# SELE_async.net
KiCad netlist of a schematic drawn in EasyEDA
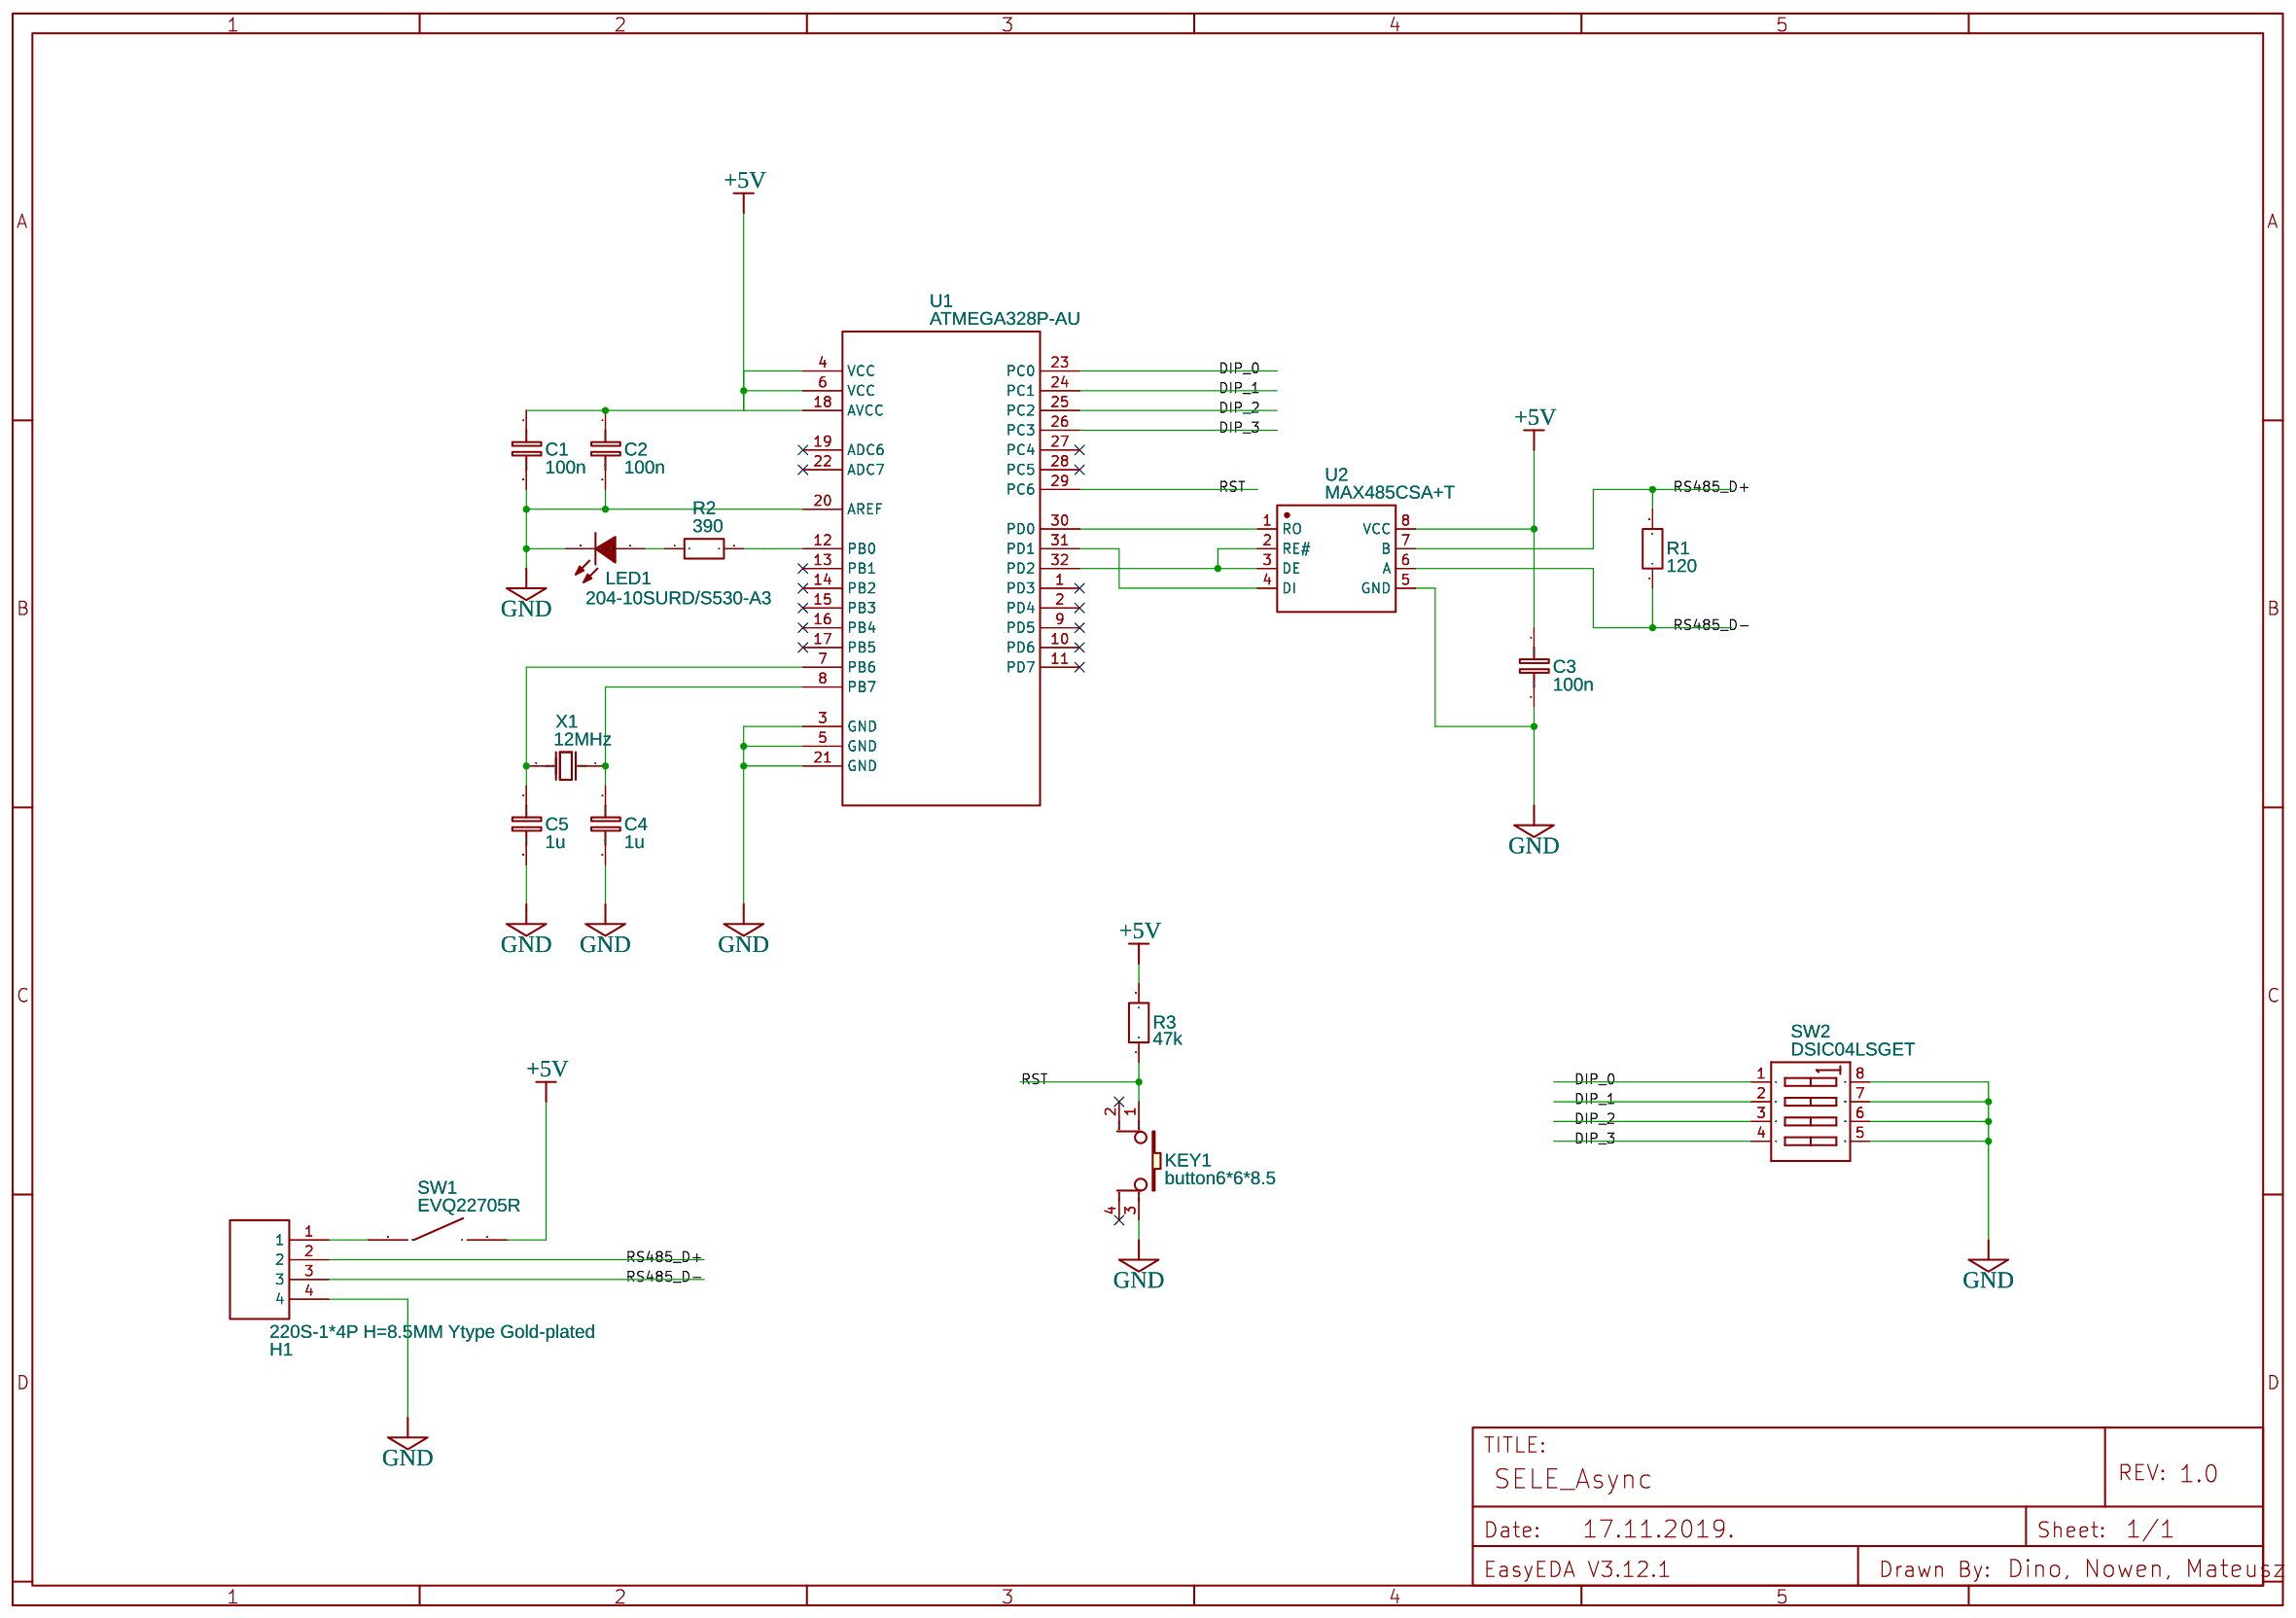
[diagram p0: schematic sheet]

(export (version "E")
  (design (tool "Eeschema 10.0.6"))
  (components
    (comp (ref "C1") (value "100n") (libsource (lib "") (part "Cap_0603_EU")))
    (comp (ref "C2") (value "100n") (libsource (lib "") (part "Cap_0603_EU")))
    (comp (ref "C3") (value "100n") (libsource (lib "") (part "Cap_0603_EU_1")))
    (comp (ref "C4") (value "1u") (libsource (lib "") (part "Cap_0603_EU")))
    (comp (ref "C5") (value "1u") (libsource (lib "") (part "Cap_0603_EU")))
    (comp (ref "H1")
      (value "220S-1*4P H=8.5MM Ytype Gold-plated")
      (fields (field (name "BOM_Supplier Part") "C124413"))
      (libsource (lib "") (part "Unknown_180_670"))
    )
    (comp (ref "KEY1")
      (value "button6*6*8.5")
      (fields (field (name "BOM_Supplier Part") "C59980"))
      (libsource (lib "") (part "Unknown_620_610"))
    )
    (comp (ref "LED1")
      (value "204-10SURD/S530-A3")
      (fields (field (name "BOM_Supplier Part") "C99772"))
      (libsource (lib "") (part "Unknown_350_300"))
    )
    (comp (ref "R1") (value "120") (libsource (lib "") (part "Res_0603(1/10W)_EU_1")))
    (comp (ref "R2") (value "390") (libsource (lib "") (part "Res_0603(1/10W)_EU")))
    (comp (ref "R3") (value "47k") (libsource (lib "") (part "Res_0603(1/10W)_EU_1")))
    (comp (ref "SW1")
      (value "EVQ22705R")
      (fields (field (name "BOM_Supplier Part") "C79156"))
      (libsource (lib "") (part "Unknown_270_650"))
    )
    (comp (ref "SW2")
      (value "DSIC04LSGET")
      (fields (field (name "BOM_Supplier Part") "C54950"))
      (libsource (lib "") (part "Unknown_960_590"))
    )
    (comp (ref "U1")
      (value "ATMEGA328P-AU")
      (fields (field (name "BOM_Supplier Part") "C14877"))
      (libsource (lib "") (part "Unknown_520_310"))
    )
    (comp (ref "U2")
      (value "MAX485CSA+T")
      (fields (field (name "BOM_Supplier Part") "C9945"))
      (libsource (lib "") (part "Unknown_720_310"))
    )
    (comp (ref "X1")
      (value "12MHz")
      (fields
        (field (name "BOM_Manufacturer Part") "X49SD12MSD2SC")
        (field (name "BOM_Supplier Part") "C16369")
      )
      (libsource (lib "") (part "X49SD12MSD2SC"))
    )
  )
  (nets
    (net (code "1") (name "+5V") (class "Default")
      (node (ref "C1") (pin "1") (pinfunction "1_1") (pintype "unspecified"))
      (node (ref "C2") (pin "1") (pinfunction "1_1") (pintype "unspecified"))
      (node (ref "C3") (pin "1") (pinfunction "1_1") (pintype "unspecified"))
      (node (ref "R3") (pin "2") (pinfunction "2_2") (pintype "unspecified"))
      (node (ref "SW1") (pin "2") (pinfunction "2_2") (pintype "input"))
      (node (ref "U1") (pin "18") (pinfunction "AVCC_18") (pintype "passive"))
      (node (ref "U1") (pin "4") (pinfunction "VCC_4") (pintype "passive"))
      (node (ref "U1") (pin "6") (pinfunction "VCC_6") (pintype "passive"))
      (node (ref "U2") (pin "8") (pinfunction "VCC_8") (pintype "unspecified"))
    )
    (net (code "2") (name "/DIP_0") (class "Default")
      (node (ref "SW2") (pin "1") (pinfunction "A1_1") (pintype "input"))
      (node (ref "U1") (pin "23") (pinfunction "PC0_23") (pintype "unspecified"))
    )
    (net (code "3") (name "/DIP_1") (class "Default")
      (node (ref "SW2") (pin "2") (pinfunction "A2_2") (pintype "input"))
      (node (ref "U1") (pin "24") (pinfunction "PC1_24") (pintype "unspecified"))
    )
    (net (code "4") (name "/DIP_2") (class "Default")
      (node (ref "SW2") (pin "3") (pinfunction "A3_3") (pintype "input"))
      (node (ref "U1") (pin "25") (pinfunction "PC2_25") (pintype "unspecified"))
    )
    (net (code "5") (name "/DIP_3") (class "Default")
      (node (ref "SW2") (pin "4") (pinfunction "A4_4") (pintype "input"))
      (node (ref "U1") (pin "26") (pinfunction "PC3_26") (pintype "unspecified"))
    )
    (net (code "6") (name "/RS485_D+") (class "Default")
      (node (ref "H1") (pin "2") (pinfunction "2_2") (pintype "unspecified"))
      (node (ref "R1") (pin "2") (pinfunction "2_2") (pintype "unspecified"))
      (node (ref "U2") (pin "7") (pinfunction "B_7") (pintype "unspecified"))
    )
    (net (code "7") (name "/RS485_D-") (class "Default")
      (node (ref "H1") (pin "3") (pinfunction "3_3") (pintype "unspecified"))
      (node (ref "R1") (pin "1") (pinfunction "1_1") (pintype "unspecified"))
      (node (ref "U2") (pin "6") (pinfunction "A_6") (pintype "unspecified"))
    )
    (net (code "8") (name "/RST") (class "Default")
      (node (ref "KEY1") (pin "1") (pinfunction "1_1") (pintype "input"))
      (node (ref "R3") (pin "1") (pinfunction "1_1") (pintype "unspecified"))
      (node (ref "U1") (pin "29") (pinfunction "PC6_29") (pintype "unspecified"))
    )
    (net (code "9") (name "GND") (class "Default")
      (node (ref "C1") (pin "2") (pinfunction "2_2") (pintype "unspecified"))
      (node (ref "C2") (pin "2") (pinfunction "2_2") (pintype "unspecified"))
      (node (ref "C3") (pin "2") (pinfunction "2_2") (pintype "unspecified"))
      (node (ref "C4") (pin "2") (pinfunction "2_2") (pintype "unspecified"))
      (node (ref "C5") (pin "2") (pinfunction "2_2") (pintype "unspecified"))
      (node (ref "H1") (pin "4") (pinfunction "4_4") (pintype "unspecified"))
      (node (ref "KEY1") (pin "3") (pinfunction "3_3") (pintype "input"))
      (node (ref "LED1") (pin "2") (pinfunction "K_2") (pintype "unspecified"))
      (node (ref "SW2") (pin "5") (pinfunction "B4_5") (pintype "input"))
      (node (ref "SW2") (pin "6") (pinfunction "B3_6") (pintype "input"))
      (node (ref "SW2") (pin "7") (pinfunction "B2_7") (pintype "input"))
      (node (ref "SW2") (pin "8") (pinfunction "B1_8") (pintype "input"))
      (node (ref "U1") (pin "20") (pinfunction "AREF_20") (pintype "input"))
      (node (ref "U1") (pin "21") (pinfunction "GND_21") (pintype "unspecified"))
      (node (ref "U1") (pin "3") (pinfunction "GND_3") (pintype "unspecified"))
      (node (ref "U1") (pin "5") (pinfunction "GND_5") (pintype "unspecified"))
      (node (ref "U2") (pin "5") (pinfunction "GND_5") (pintype "unspecified"))
    )
    (net (code "10") (name "Net-(H1-Pad1)") (class "Default")
      (node (ref "H1") (pin "1") (pinfunction "1_1") (pintype "unspecified"))
      (node (ref "SW1") (pin "1") (pinfunction "1_1") (pintype "input"))
    )
    (net (code "11") (name "Net-(LED1-A)") (class "Default")
      (node (ref "LED1") (pin "1") (pinfunction "A_1") (pintype "unspecified"))
      (node (ref "R2") (pin "1") (pinfunction "1_1") (pintype "unspecified"))
    )
    (net (code "12") (name "Net-(U1-PB0)") (class "Default")
      (node (ref "R2") (pin "2") (pinfunction "2_2") (pintype "unspecified"))
      (node (ref "U1") (pin "12") (pinfunction "PB0_12") (pintype "unspecified"))
    )
    (net (code "13") (name "Net-(U1-PB6)") (class "Default")
      (node (ref "C5") (pin "1") (pinfunction "1_1") (pintype "unspecified"))
      (node (ref "U1") (pin "7") (pinfunction "PB6_7") (pintype "unspecified"))
      (node (ref "X1") (pin "2") (pinfunction "OSC2_2") (pintype "input"))
    )
    (net (code "14") (name "Net-(U1-PB7)") (class "Default")
      (node (ref "C4") (pin "1") (pinfunction "1_1") (pintype "unspecified"))
      (node (ref "U1") (pin "8") (pinfunction "PB7_8") (pintype "unspecified"))
      (node (ref "X1") (pin "1") (pinfunction "OSC1_1") (pintype "input"))
    )
    (net (code "15") (name "Net-(U1-PD0)") (class "Default")
      (node (ref "U1") (pin "30") (pinfunction "PD0_30") (pintype "unspecified"))
      (node (ref "U2") (pin "1") (pinfunction "RO_1") (pintype "unspecified"))
    )
    (net (code "16") (name "Net-(U1-PD1)") (class "Default")
      (node (ref "U1") (pin "31") (pinfunction "PD1_31") (pintype "unspecified"))
      (node (ref "U2") (pin "4") (pinfunction "DI_4") (pintype "unspecified"))
    )
    (net (code "17") (name "Net-(U1-PD2)") (class "Default")
      (node (ref "U1") (pin "32") (pinfunction "PD2_32") (pintype "unspecified"))
      (node (ref "U2") (pin "2") (pinfunction "RE#_2") (pintype "unspecified"))
      (node (ref "U2") (pin "3") (pinfunction "DE_3") (pintype "unspecified"))
    )
    (net (code "18") (name "unconnected-(KEY1-Pad2)") (class "Default")
      (node (ref "KEY1") (pin "2") (pinfunction "2_2") (pintype "input+no_connect"))
    )
    (net (code "19") (name "unconnected-(KEY1-Pad4)") (class "Default")
      (node (ref "KEY1") (pin "4") (pinfunction "4_4") (pintype "input+no_connect"))
    )
    (net (code "20") (name "unconnected-(U1-ADC6-Pad19)") (class "Default")
      (node (ref "U1") (pin "19") (pinfunction "ADC6_19") (pintype "input+no_connect"))
    )
    (net (code "21") (name "unconnected-(U1-ADC7-Pad22)") (class "Default")
      (node (ref "U1") (pin "22") (pinfunction "ADC7_22") (pintype "input+no_connect"))
    )
    (net (code "22") (name "unconnected-(U1-PB1-Pad13)") (class "Default")
      (node (ref "U1") (pin "13") (pinfunction "PB1_13") (pintype "unspecified+no_connect"))
    )
    (net (code "23") (name "unconnected-(U1-PB2-Pad14)") (class "Default")
      (node (ref "U1") (pin "14") (pinfunction "PB2_14") (pintype "unspecified+no_connect"))
    )
    (net (code "24") (name "unconnected-(U1-PB3-Pad15)") (class "Default")
      (node (ref "U1") (pin "15") (pinfunction "PB3_15") (pintype "unspecified+no_connect"))
    )
    (net (code "25") (name "unconnected-(U1-PB4-Pad16)") (class "Default")
      (node (ref "U1") (pin "16") (pinfunction "PB4_16") (pintype "unspecified+no_connect"))
    )
    (net (code "26") (name "unconnected-(U1-PB5-Pad17)") (class "Default")
      (node (ref "U1") (pin "17") (pinfunction "PB5_17") (pintype "unspecified+no_connect"))
    )
    (net (code "27") (name "unconnected-(U1-PC4-Pad27)") (class "Default")
      (node (ref "U1") (pin "27") (pinfunction "PC4_27") (pintype "unspecified+no_connect"))
    )
    (net (code "28") (name "unconnected-(U1-PC5-Pad28)") (class "Default")
      (node (ref "U1") (pin "28") (pinfunction "PC5_28") (pintype "unspecified+no_connect"))
    )
    (net (code "29") (name "unconnected-(U1-PD3-Pad1)") (class "Default")
      (node (ref "U1") (pin "1") (pinfunction "PD3_1") (pintype "unspecified+no_connect"))
    )
    (net (code "30") (name "unconnected-(U1-PD4-Pad2)") (class "Default")
      (node (ref "U1") (pin "2") (pinfunction "PD4_2") (pintype "unspecified+no_connect"))
    )
    (net (code "31") (name "unconnected-(U1-PD5-Pad9)") (class "Default")
      (node (ref "U1") (pin "9") (pinfunction "PD5_9") (pintype "unspecified+no_connect"))
    )
    (net (code "32") (name "unconnected-(U1-PD6-Pad10)") (class "Default")
      (node (ref "U1") (pin "10") (pinfunction "PD6_10") (pintype "unspecified+no_connect"))
    )
    (net (code "33") (name "unconnected-(U1-PD7-Pad11)") (class "Default")
      (node (ref "U1") (pin "11") (pinfunction "PD7_11") (pintype "unspecified+no_connect"))
    )
  )
)
